# RSD_M1_HELMET_UNIT_POWER_V2.net
KiCad netlist of a schematic drawn in Altium Designer
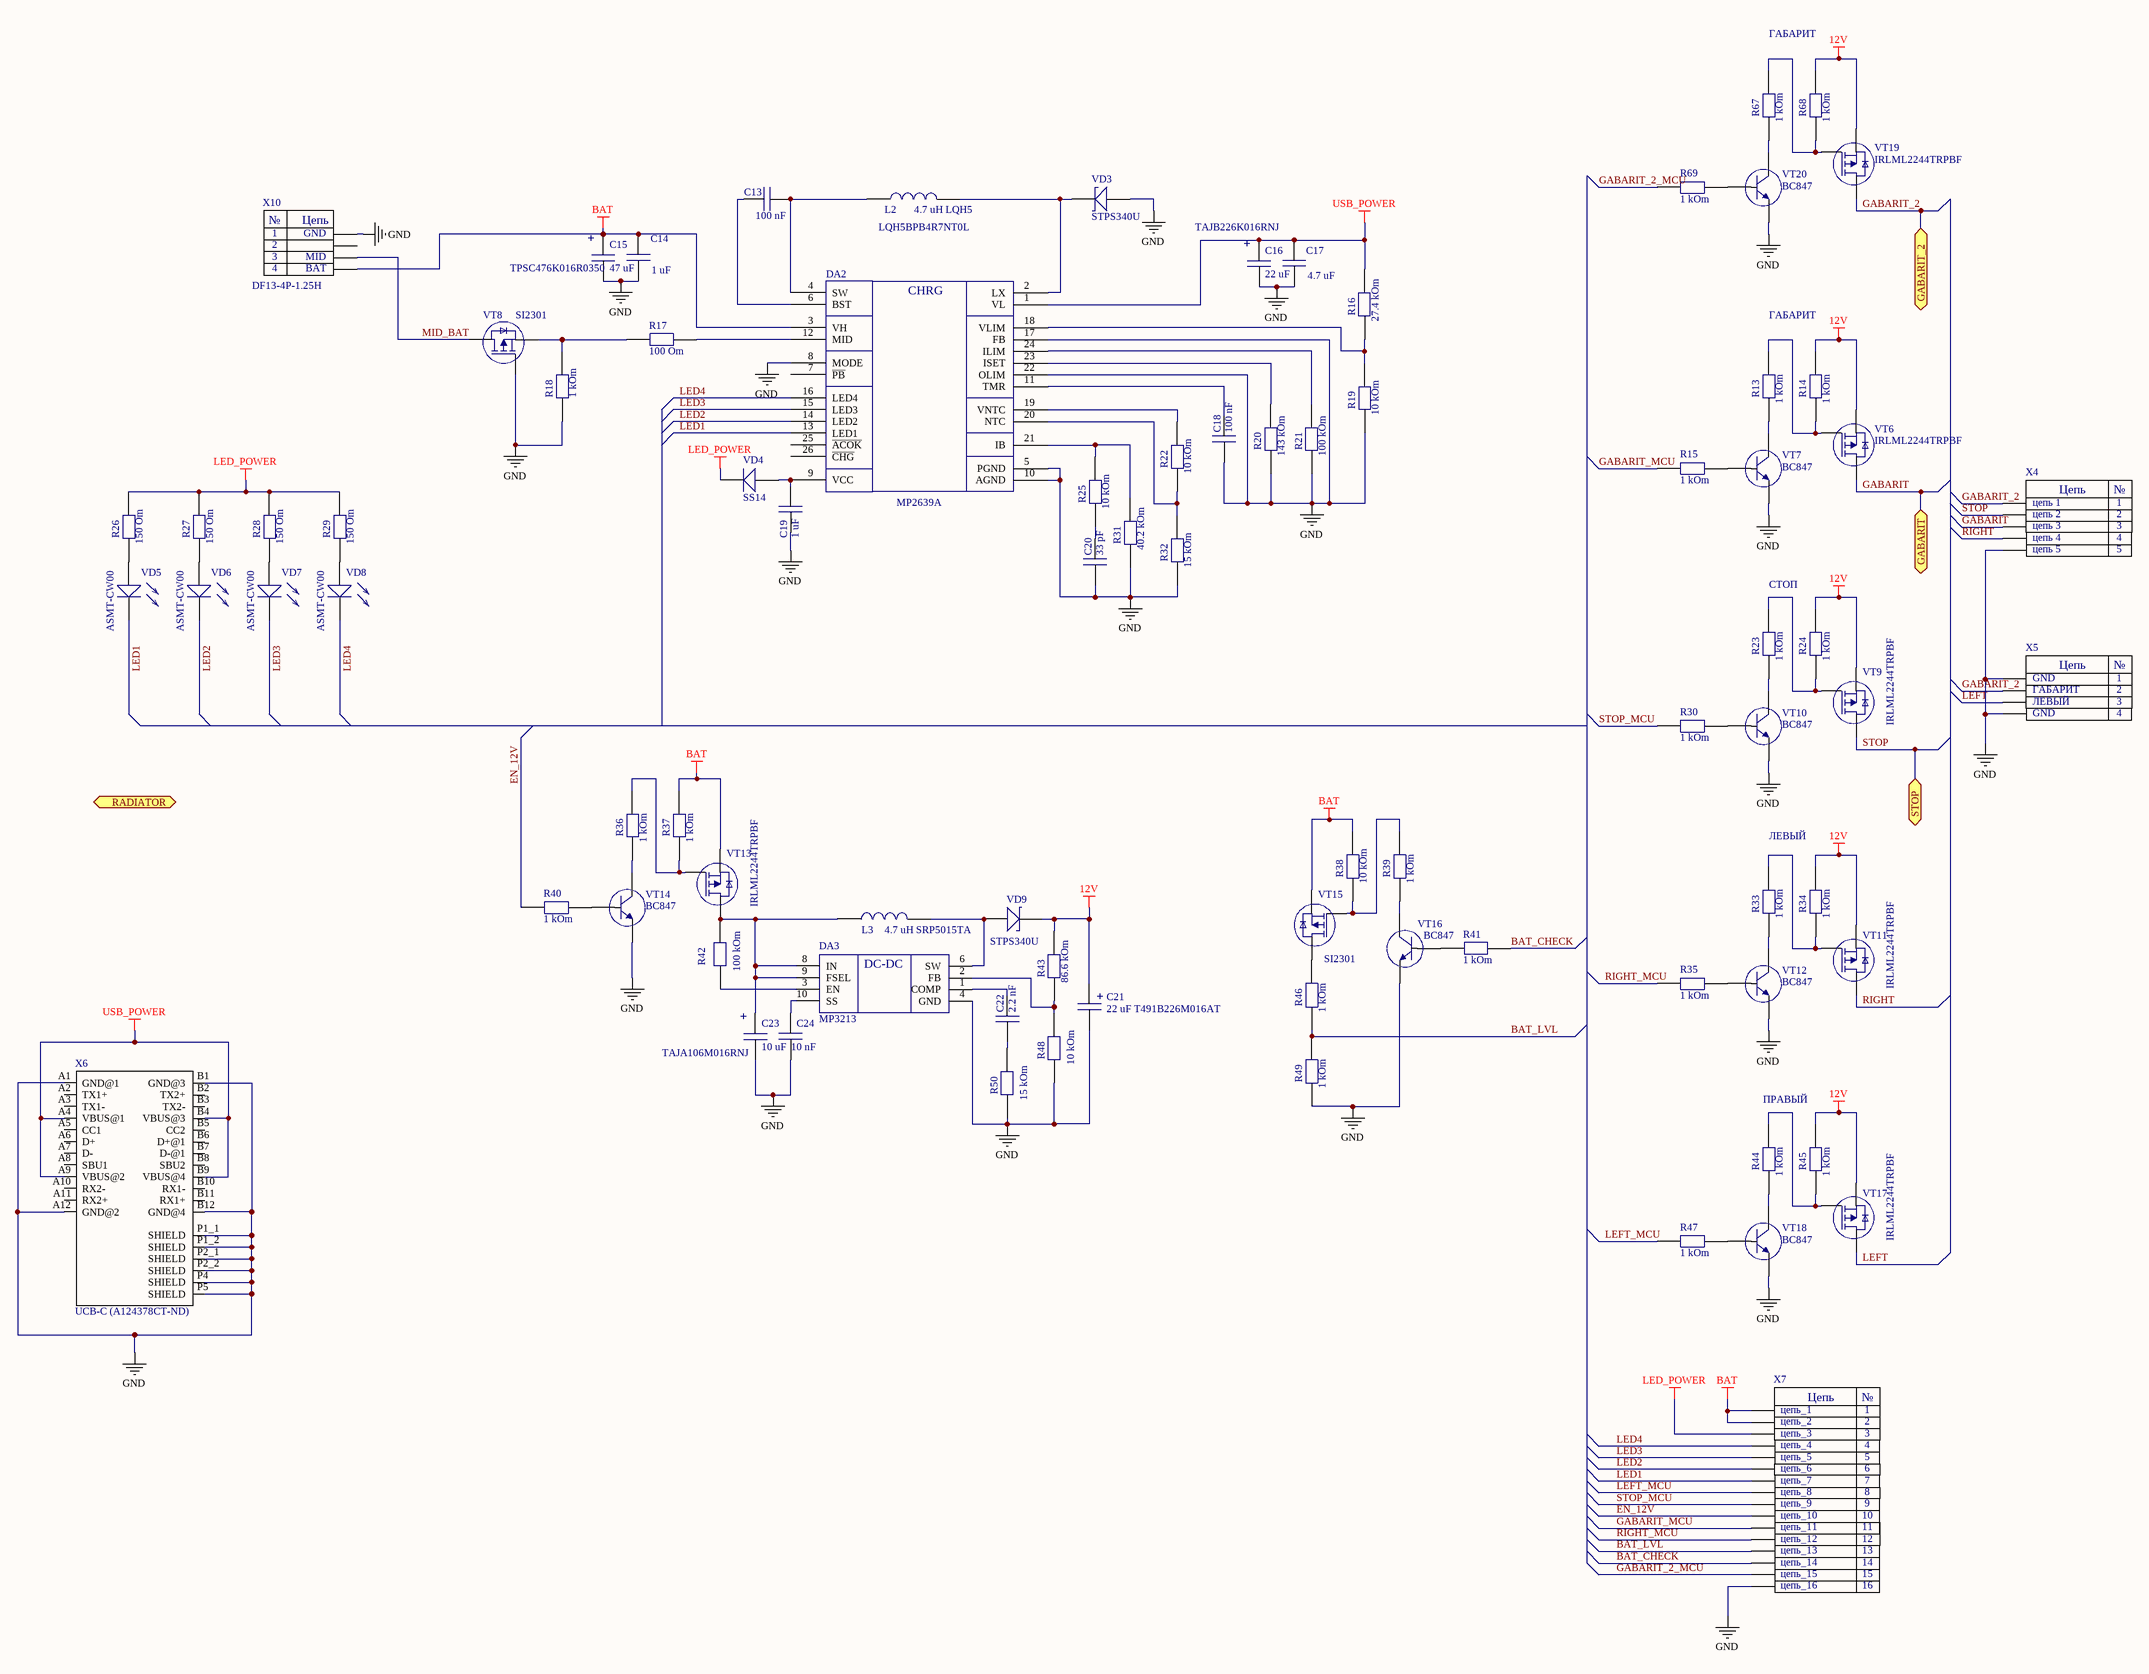
[diagram p0: RSD_M1_HELMET_UNIT_POWER_V2.SchDoc]

(export (version "E")
  (design (tool "Eeschema 10.0.6"))
  (components
    (comp (ref "C13")
      (value "100 nF")
      (footprint "CAP0603")
      (fields (field (name "Comment") "Capacitor"))
      (libsource (lib "my_library") (part "Capacitor"))
    )
    (comp (ref "C14")
      (value "1 uF")
      (footprint "CAP0603")
      (fields (field (name "Comment") "Capacitor"))
      (libsource (lib "my_library") (part "Capacitor"))
    )
    (comp (ref "C15")
      (value "47 uF")
      (footprint "tantal_case_B")
      (fields (field (name "ALTIUM_VALUE") "TPSC476K016R0350"))
      (libsource (lib "my_library") (part "Capacitor_Polar"))
    )
    (comp (ref "C16")
      (value "22 uF")
      (footprint "tantal_case_B")
      (fields (field (name "ALTIUM_VALUE") "TAJB226K016RNJ"))
      (libsource (lib "my_library") (part "Capacitor_Polar"))
    )
    (comp (ref "C17")
      (value "4.7 uF")
      (footprint "CAP0603")
      (fields (field (name "Comment") "Capacitor"))
      (libsource (lib "my_library") (part "Capacitor"))
    )
    (comp (ref "C18")
      (value "100 nF")
      (footprint "CAP0603")
      (fields (field (name "Comment") "Capacitor"))
      (libsource (lib "my_library") (part "Capacitor"))
    )
    (comp (ref "C19")
      (value "1 uF")
      (footprint "CAP0603")
      (fields (field (name "Comment") "Capacitor"))
      (libsource (lib "my_library") (part "Capacitor"))
    )
    (comp (ref "C20")
      (value "33 pF")
      (footprint "CAP0603")
      (fields (field (name "Comment") "Capacitor"))
      (libsource (lib "my_library") (part "Capacitor"))
    )
    (comp (ref "C21")
      (value "22 uF T491B226M016AT")
      (footprint "tantal_case_B")
      (fields (field (name "Comment") "Capacitor_Polar"))
      (libsource (lib "my_library") (part "Capacitor_Polar"))
    )
    (comp (ref "C22")
      (value "2.2 nF")
      (footprint "CAP0603")
      (fields (field (name "Comment") "Capacitor"))
      (libsource (lib "my_library") (part "Capacitor"))
    )
    (comp (ref "C23")
      (value "10 uF")
      (footprint "tantal_case_A")
      (fields (field (name "ALTIUM_VALUE") "TAJA106M016RNJ"))
      (libsource (lib "my_library") (part "Capacitor_Polar"))
    )
    (comp (ref "C24")
      (value "10 nF")
      (footprint "CAP0603")
      (fields (field (name "Comment") "Capacitor"))
      (libsource (lib "my_library") (part "Capacitor"))
    )
    (comp (ref "DA2")
      (value "MP2639A")
      (footprint "MP2639")
      (fields (field (name "Comment") "MP2639"))
      (libsource (lib "my_library") (part "MP2639"))
    )
    (comp (ref "DA3") (value "MP3213") (footprint "MP3213") (libsource (lib "my_library") (part "MP3213")))
    (comp (ref "L2")
      (value "4.7 uH LQH5")
      (footprint "LQH5BP")
      (fields (field (name "PN") "LQH5BPB4R7NT0L") (field (name "Comment") "coil"))
      (libsource (lib "my_library") (part "coil"))
    )
    (comp (ref "L3")
      (value "4.7 uH SRP5015TA")
      (footprint "inductor_SRP5015TA")
      (fields (field (name "Comment") "coil"))
      (libsource (lib "my_library") (part "coil"))
    )
    (comp (ref "R13")
      (value "1 kOm")
      (footprint "Res0603")
      (fields (field (name "Comment") "Resistor"))
      (libsource (lib "my_library") (part "Resistor"))
    )
    (comp (ref "R14")
      (value "1 kOm")
      (footprint "Res0603")
      (fields (field (name "Comment") "Resistor"))
      (libsource (lib "my_library") (part "Resistor"))
    )
    (comp (ref "R15")
      (value "1 kOm")
      (footprint "Res0603")
      (fields (field (name "Comment") "Resistor"))
      (libsource (lib "my_library") (part "Resistor"))
    )
    (comp (ref "R16")
      (value "27.4 kOm")
      (footprint "Res0603")
      (fields (field (name "Comment") "Resistor"))
      (libsource (lib "my_library") (part "Resistor"))
    )
    (comp (ref "R17")
      (value "100 Om")
      (footprint "Res0603")
      (fields (field (name "Comment") "Resistor"))
      (libsource (lib "my_library") (part "Resistor"))
    )
    (comp (ref "R18")
      (value "1 kOm")
      (footprint "Res0603")
      (fields (field (name "Comment") "Resistor"))
      (libsource (lib "my_library") (part "Resistor"))
    )
    (comp (ref "R19")
      (value "10 kOm")
      (footprint "Res0603")
      (fields (field (name "Comment") "Resistor"))
      (libsource (lib "my_library") (part "Resistor"))
    )
    (comp (ref "R20")
      (value "143 kOm")
      (footprint "Res0603")
      (fields (field (name "Comment") "Resistor"))
      (libsource (lib "my_library") (part "Resistor"))
    )
    (comp (ref "R21")
      (value "100 kOm")
      (footprint "Res0603")
      (fields (field (name "Comment") "Resistor"))
      (libsource (lib "my_library") (part "Resistor"))
    )
    (comp (ref "R22")
      (value "10 kOm")
      (footprint "Res0603")
      (fields (field (name "Comment") "Resistor"))
      (libsource (lib "my_library") (part "Resistor"))
    )
    (comp (ref "R23")
      (value "1 kOm")
      (footprint "Res0603")
      (fields (field (name "Comment") "Resistor"))
      (libsource (lib "my_library") (part "Resistor"))
    )
    (comp (ref "R24")
      (value "1 kOm")
      (footprint "Res0603")
      (fields (field (name "Comment") "Resistor"))
      (libsource (lib "my_library") (part "Resistor"))
    )
    (comp (ref "R25")
      (value "10 kOm")
      (footprint "Res0603")
      (fields (field (name "Comment") "Resistor"))
      (libsource (lib "my_library") (part "Resistor"))
    )
    (comp (ref "R26")
      (value "150 Om")
      (footprint "Res0603")
      (fields (field (name "Comment") "Resistor"))
      (libsource (lib "my_library") (part "Resistor"))
    )
    (comp (ref "R27")
      (value "150 Om")
      (footprint "Res0603")
      (fields (field (name "Comment") "Resistor"))
      (libsource (lib "my_library") (part "Resistor"))
    )
    (comp (ref "R28")
      (value "150 Om")
      (footprint "Res0603")
      (fields (field (name "Comment") "Resistor"))
      (libsource (lib "my_library") (part "Resistor"))
    )
    (comp (ref "R29")
      (value "150 Om")
      (footprint "Res0603")
      (fields (field (name "Comment") "Resistor"))
      (libsource (lib "my_library") (part "Resistor"))
    )
    (comp (ref "R30")
      (value "1 kOm")
      (footprint "Res0603")
      (fields (field (name "Comment") "Resistor"))
      (libsource (lib "my_library") (part "Resistor"))
    )
    (comp (ref "R31")
      (value "40.2 kOm")
      (footprint "Res0603")
      (fields (field (name "Comment") "Resistor"))
      (libsource (lib "my_library") (part "Resistor"))
    )
    (comp (ref "R32")
      (value "15 kOm")
      (footprint "Res0603")
      (fields (field (name "Comment") "Resistor"))
      (libsource (lib "my_library") (part "Resistor"))
    )
    (comp (ref "R33")
      (value "1 kOm")
      (footprint "Res0603")
      (fields (field (name "Comment") "Resistor"))
      (libsource (lib "my_library") (part "Resistor"))
    )
    (comp (ref "R34")
      (value "1 kOm")
      (footprint "Res0603")
      (fields (field (name "Comment") "Resistor"))
      (libsource (lib "my_library") (part "Resistor"))
    )
    (comp (ref "R35")
      (value "1 kOm")
      (footprint "Res0603")
      (fields (field (name "Comment") "Resistor"))
      (libsource (lib "my_library") (part "Resistor"))
    )
    (comp (ref "R36")
      (value "1 kOm")
      (footprint "Res0603")
      (fields (field (name "Comment") "Resistor"))
      (libsource (lib "my_library") (part "Resistor"))
    )
    (comp (ref "R37")
      (value "1 kOm")
      (footprint "Res0603")
      (fields (field (name "Comment") "Resistor"))
      (libsource (lib "my_library") (part "Resistor"))
    )
    (comp (ref "R38")
      (value "10 kOm")
      (footprint "Res0603")
      (fields (field (name "Comment") "Resistor"))
      (libsource (lib "my_library") (part "Resistor"))
    )
    (comp (ref "R39")
      (value "1 kOm")
      (footprint "Res0603")
      (fields (field (name "Comment") "Resistor"))
      (libsource (lib "my_library") (part "Resistor"))
    )
    (comp (ref "R40")
      (value "1 kOm")
      (footprint "Res0603")
      (fields (field (name "Comment") "Resistor"))
      (libsource (lib "my_library") (part "Resistor"))
    )
    (comp (ref "R41")
      (value "1 kOm")
      (footprint "Res0603")
      (fields (field (name "Comment") "Resistor"))
      (libsource (lib "my_library") (part "Resistor"))
    )
    (comp (ref "R42")
      (value "100 kOm")
      (footprint "Res0603")
      (fields (field (name "Comment") "Resistor"))
      (libsource (lib "my_library") (part "Resistor"))
    )
    (comp (ref "R43")
      (value "86.6 kOm")
      (footprint "Res0603")
      (fields (field (name "Comment") "Resistor"))
      (libsource (lib "my_library") (part "Resistor"))
    )
    (comp (ref "R44")
      (value "1 kOm")
      (footprint "Res0603")
      (fields (field (name "Comment") "Resistor"))
      (libsource (lib "my_library") (part "Resistor"))
    )
    (comp (ref "R45")
      (value "1 kOm")
      (footprint "Res0603")
      (fields (field (name "Comment") "Resistor"))
      (libsource (lib "my_library") (part "Resistor"))
    )
    (comp (ref "R46")
      (value "1 kOm")
      (footprint "Res0603")
      (fields (field (name "Comment") "Resistor"))
      (libsource (lib "my_library") (part "Resistor"))
    )
    (comp (ref "R47")
      (value "1 kOm")
      (footprint "Res0603")
      (fields (field (name "Comment") "Resistor"))
      (libsource (lib "my_library") (part "Resistor"))
    )
    (comp (ref "R48")
      (value "10 kOm")
      (footprint "Res0603")
      (fields (field (name "Comment") "Resistor"))
      (libsource (lib "my_library") (part "Resistor"))
    )
    (comp (ref "R49")
      (value "1 kOm")
      (footprint "Res0603")
      (fields (field (name "Comment") "Resistor"))
      (libsource (lib "my_library") (part "Resistor"))
    )
    (comp (ref "R50")
      (value "15 kOm")
      (footprint "Res0603")
      (fields (field (name "Comment") "Resistor"))
      (libsource (lib "my_library") (part "Resistor"))
    )
    (comp (ref "R67")
      (value "1 kOm")
      (footprint "Res0603")
      (fields (field (name "Comment") "Resistor"))
      (libsource (lib "my_library") (part "Resistor"))
    )
    (comp (ref "R68")
      (value "1 kOm")
      (footprint "Res0603")
      (fields (field (name "Comment") "Resistor"))
      (libsource (lib "my_library") (part "Resistor"))
    )
    (comp (ref "R69")
      (value "1 kOm")
      (footprint "Res0603")
      (fields (field (name "Comment") "Resistor"))
      (libsource (lib "my_library") (part "Resistor"))
    )
    (comp (ref "VD3")
      (value "STPS340U")
      (footprint "SMB1")
      (fields (field (name "Comment") "Schottky"))
      (libsource (lib "my_library") (part "Schottky"))
    )
    (comp (ref "VD4")
      (value "SS14")
      (footprint "SMA-F")
      (fields (field (name "Comment") "Diode"))
      (libsource (lib "my_library") (part "Diode"))
    )
    (comp (ref "VD5")
      (value "ASMT-CW00")
      (footprint "LED 0603")
      (fields (field (name "Comment") "LED"))
      (libsource (lib "my_library") (part "LED"))
    )
    (comp (ref "VD6")
      (value "ASMT-CW00")
      (footprint "LED 0603")
      (fields (field (name "Comment") "LED"))
      (libsource (lib "my_library") (part "LED"))
    )
    (comp (ref "VD7")
      (value "ASMT-CW00")
      (footprint "LED 0603")
      (fields (field (name "Comment") "LED"))
      (libsource (lib "my_library") (part "LED"))
    )
    (comp (ref "VD8")
      (value "ASMT-CW00")
      (footprint "LED 0603")
      (fields (field (name "Comment") "LED"))
      (libsource (lib "my_library") (part "LED"))
    )
    (comp (ref "VD9")
      (value "STPS340U")
      (footprint "SMB1")
      (fields (field (name "Comment") "Schottky"))
      (libsource (lib "my_library") (part "Schottky"))
    )
    (comp (ref "VT6")
      (value "IRLML2244TRPBF")
      (footprint "SOT 23")
      (fields (field (name "Comment") "MOSFET-P"))
      (libsource (lib "my_library") (part "MOSFET-P"))
    )
    (comp (ref "VT7")
      (value "BC847")
      (footprint "SOT 23")
      (fields (field (name "Comment") "NPN"))
      (libsource (lib "") (part "NPN_1"))
    )
    (comp (ref "VT8")
      (value "SI2301")
      (footprint "SOT 23")
      (fields (field (name "Comment") "MOSFET-P"))
      (libsource (lib "") (part "MOSFET-P_1"))
    )
    (comp (ref "VT9")
      (value "IRLML2244TRPBF")
      (footprint "SOT 23")
      (fields (field (name "Comment") "MOSFET-P"))
      (libsource (lib "my_library") (part "MOSFET-P"))
    )
    (comp (ref "VT10")
      (value "BC847")
      (footprint "SOT 23")
      (fields (field (name "Comment") "NPN"))
      (libsource (lib "") (part "NPN_1"))
    )
    (comp (ref "VT11")
      (value "IRLML2244TRPBF")
      (footprint "SOT 23")
      (fields (field (name "Comment") "MOSFET-P"))
      (libsource (lib "my_library") (part "MOSFET-P"))
    )
    (comp (ref "VT12")
      (value "BC847")
      (footprint "SOT 23")
      (fields (field (name "Comment") "NPN"))
      (libsource (lib "") (part "NPN_1"))
    )
    (comp (ref "VT13")
      (value "IRLML2244TRPBF")
      (footprint "SOT 23")
      (fields (field (name "Comment") "MOSFET-P"))
      (libsource (lib "my_library") (part "MOSFET-P"))
    )
    (comp (ref "VT14")
      (value "BC847")
      (footprint "SOT 23")
      (fields (field (name "Comment") "NPN"))
      (libsource (lib "") (part "NPN_1"))
    )
    (comp (ref "VT15")
      (value "SI2301")
      (footprint "SOT 23")
      (fields (field (name "Comment") "MOSFET-P"))
      (libsource (lib "my_library") (part "MOSFET-P"))
    )
    (comp (ref "VT16")
      (value "BC847")
      (footprint "SOT 23")
      (fields (field (name "Comment") "NPN"))
      (libsource (lib "my_library") (part "NPN"))
    )
    (comp (ref "VT17")
      (value "IRLML2244TRPBF")
      (footprint "SOT 23")
      (fields (field (name "Comment") "MOSFET-P"))
      (libsource (lib "my_library") (part "MOSFET-P"))
    )
    (comp (ref "VT18")
      (value "BC847")
      (footprint "SOT 23")
      (fields (field (name "Comment") "NPN"))
      (libsource (lib "") (part "NPN_1"))
    )
    (comp (ref "VT19")
      (value "IRLML2244TRPBF")
      (footprint "SOT 23")
      (fields (field (name "Comment") "MOSFET-P"))
      (libsource (lib "my_library") (part "MOSFET-P"))
    )
    (comp (ref "VT20")
      (value "BC847")
      (footprint "SOT 23")
      (fields (field (name "Comment") "NPN"))
      (libsource (lib "") (part "NPN_1"))
    )
    (comp (ref "X4")
      (value "FPC_connector_5_1")
      (footprint "FPC_5_1")
      (fields
        (field (name "1") "цепь 1")
        (field (name "2") "цепь 2")
        (field (name "3") "цепь 3")
        (field (name "4") "цепь 4")
        (field (name "5") "цепь 5")
      )
      (libsource (lib "my_library") (part "FPC_connector_5_1"))
    )
    (comp (ref "X5")
      (value "FPC_connector_4_1")
      (footprint "FPC_4_1")
      (fields
        (field (name "1") "GND")
        (field (name "2") "ГАБАРИТ")
        (field (name "3") "ЛЕВЫЙ")
        (field (name "4") "GND")
      )
      (libsource (lib "my_library") (part "FPC_connector_4_1"))
    )
    (comp (ref "X6")
      (value "UCB-C (A124378CT-ND)")
      (footprint "USB-C")
      (fields (field (name "Comment") "UCB-C"))
      (libsource (lib "my_library") (part "UCB-C"))
    )
    (comp (ref "X7")
      (value "FPC_connector_16")
      (footprint "FPC_16_0.5")
      (fields
        (field (name "16") "цепь_16")
        (field (name "1") "цепь_1")
        (field (name "2") "цепь_2")
        (field (name "3") "цепь_3")
        (field (name "4") "цепь_4")
        (field (name "5") "цепь_5")
        (field (name "6") "цепь_6")
        (field (name "7") "цепь_7")
        (field (name "8") "цепь_8")
        (field (name "9") "цепь_9")
        (field (name "10") "цепь_10")
        (field (name "11") "цепь_11")
        (field (name "12") "цепь_12")
        (field (name "13") "цепь_13")
        (field (name "14") "цепь_14")
        (field (name "15") "цепь_15")
      )
      (libsource (lib "my_library") (part "FPC_connector_16"))
    )
    (comp (ref "X10")
      (value "DF13-4P-1.25H")
      (footprint "bat_conn")
      (fields
        (field (name "1") "GND")
        (field (name "3") "MID")
        (field (name "4") "BAT")
        (field (name "Comment") "BATTERY")
      )
      (libsource (lib "my_library") (part "SWDIO"))
    )
  )
  (nets
    (net (code "1") (name "/BAT_CHECK") (class "Default")
      (node (ref "R41") (pin "2") (pinfunction "2_2") (pintype "passive"))
      (node (ref "X7") (pin "14") (pinfunction "14_14") (pintype "passive"))
    )
    (net (code "2") (name "/BAT_LVL") (class "Default")
      (node (ref "R46") (pin "1") (pinfunction "1_1") (pintype "passive"))
      (node (ref "R49") (pin "2") (pinfunction "2_2") (pintype "passive"))
      (node (ref "X7") (pin "13") (pinfunction "13_13") (pintype "passive"))
    )
    (net (code "3") (name "/EN_12V") (class "Default")
      (node (ref "R40") (pin "2") (pinfunction "2_2") (pintype "passive"))
      (node (ref "X7") (pin "10") (pinfunction "10_10") (pintype "passive"))
    )
    (net (code "4") (name "/GABARIT") (class "Default")
      (node (ref "VT6") (pin "D") (pintype "passive"))
      (node (ref "X4") (pin "3") (pinfunction "3_3") (pintype "passive"))
    )
    (net (code "5") (name "/GABARIT_2") (class "Default")
      (node (ref "VT19") (pin "D") (pintype "passive"))
      (node (ref "X4") (pin "1") (pinfunction "1_1") (pintype "passive"))
      (node (ref "X5") (pin "2") (pinfunction "2_2") (pintype "passive"))
    )
    (net (code "6") (name "/GABARIT_2_MCU") (class "Default")
      (node (ref "R69") (pin "2") (pinfunction "2_2") (pintype "passive"))
      (node (ref "X7") (pin "15") (pinfunction "15_15") (pintype "passive"))
    )
    (net (code "7") (name "/GABARIT_MCU") (class "Default")
      (node (ref "R15") (pin "2") (pinfunction "2_2") (pintype "passive"))
      (node (ref "X7") (pin "11") (pinfunction "11_11") (pintype "passive"))
    )
    (net (code "8") (name "/LED1") (class "Default")
      (node (ref "DA2") (pin "13") (pinfunction "LED1_13") (pintype "passive"))
      (node (ref "VD5") (pin "1") (pinfunction "1_1") (pintype "passive"))
      (node (ref "X7") (pin "7") (pinfunction "7_7") (pintype "passive"))
    )
    (net (code "9") (name "/LED2") (class "Default")
      (node (ref "DA2") (pin "14") (pinfunction "LED2_14") (pintype "passive"))
      (node (ref "VD6") (pin "1") (pinfunction "1_1") (pintype "passive"))
      (node (ref "X7") (pin "6") (pinfunction "6_6") (pintype "passive"))
    )
    (net (code "10") (name "/LED3") (class "Default")
      (node (ref "DA2") (pin "15") (pinfunction "LED3_15") (pintype "passive"))
      (node (ref "VD7") (pin "1") (pinfunction "1_1") (pintype "passive"))
      (node (ref "X7") (pin "5") (pinfunction "5_5") (pintype "passive"))
    )
    (net (code "11") (name "/LED4") (class "Default")
      (node (ref "DA2") (pin "16") (pinfunction "LED4_16") (pintype "passive"))
      (node (ref "VD8") (pin "1") (pinfunction "1_1") (pintype "passive"))
      (node (ref "X7") (pin "4") (pinfunction "4_4") (pintype "passive"))
    )
    (net (code "12") (name "/LEFT") (class "Default")
      (node (ref "VT17") (pin "D") (pintype "passive"))
      (node (ref "X5") (pin "3") (pinfunction "3_3") (pintype "passive"))
    )
    (net (code "13") (name "/LEFT_MCU") (class "Default")
      (node (ref "R47") (pin "2") (pinfunction "2_2") (pintype "passive"))
      (node (ref "X7") (pin "8") (pinfunction "8_8") (pintype "passive"))
    )
    (net (code "14") (name "/MID_BAT") (class "Default")
      (node (ref "VT8") (pin "D") (pintype "passive"))
      (node (ref "X10") (pin "3") (pinfunction "3_3") (pintype "passive"))
    )
    (net (code "16") (name "/RIGHT") (class "Default")
      (node (ref "VT11") (pin "D") (pintype "passive"))
      (node (ref "X4") (pin "4") (pinfunction "4_4") (pintype "passive"))
    )
    (net (code "17") (name "/RIGHT_MCU") (class "Default")
      (node (ref "R35") (pin "2") (pinfunction "2_2") (pintype "passive"))
      (node (ref "X7") (pin "12") (pinfunction "12_12") (pintype "passive"))
    )
    (net (code "18") (name "/STOP") (class "Default")
      (node (ref "VT9") (pin "D") (pintype "passive"))
      (node (ref "X4") (pin "2") (pinfunction "2_2") (pintype "passive"))
    )
    (net (code "19") (name "/STOP_MCU") (class "Default")
      (node (ref "R30") (pin "2") (pinfunction "2_2") (pintype "passive"))
      (node (ref "X7") (pin "9") (pinfunction "9_9") (pintype "passive"))
    )
    (net (code "20") (name "12V") (class "Default")
      (node (ref "C21") (pin "1") (pinfunction "1_1") (pintype "passive"))
      (node (ref "R14") (pin "2") (pinfunction "2_2") (pintype "passive"))
      (node (ref "R24") (pin "2") (pinfunction "2_2") (pintype "passive"))
      (node (ref "R34") (pin "2") (pinfunction "2_2") (pintype "passive"))
      (node (ref "R43") (pin "1") (pinfunction "1_1") (pintype "passive"))
      (node (ref "R45") (pin "2") (pinfunction "2_2") (pintype "passive"))
      (node (ref "R68") (pin "2") (pinfunction "2_2") (pintype "passive"))
      (node (ref "VD9") (pin "1") (pinfunction "1_1") (pintype "passive"))
      (node (ref "VT11") (pin "S") (pintype "passive"))
      (node (ref "VT17") (pin "S") (pintype "passive"))
      (node (ref "VT19") (pin "S") (pintype "passive"))
      (node (ref "VT6") (pin "S") (pintype "passive"))
      (node (ref "VT9") (pin "S") (pintype "passive"))
    )
    (net (code "21") (name "BAT") (class "Default")
      (node (ref "C14") (pin "2") (pinfunction "2_2") (pintype "passive"))
      (node (ref "C15") (pin "1") (pinfunction "1_1") (pintype "passive"))
      (node (ref "DA2") (pin "3") (pinfunction "VH_3") (pintype "passive"))
      (node (ref "R37") (pin "2") (pinfunction "2_2") (pintype "passive"))
      (node (ref "R38") (pin "2") (pinfunction "2_2") (pintype "passive"))
      (node (ref "VT13") (pin "S") (pintype "passive"))
      (node (ref "VT15") (pin "S") (pintype "passive"))
      (node (ref "X10") (pin "4") (pinfunction "4_4") (pintype "passive"))
      (node (ref "X7") (pin "1") (pinfunction "1_1") (pintype "passive"))
      (node (ref "X7") (pin "2") (pinfunction "2_2") (pintype "passive"))
    )
    (net (code "22") (name "GND") (class "Default")
      (node (ref "C14") (pin "1") (pinfunction "1_1") (pintype "passive"))
      (node (ref "C15") (pin "2") (pinfunction "2_2") (pintype "passive"))
      (node (ref "C16") (pin "2") (pinfunction "2_2") (pintype "passive"))
      (node (ref "C17") (pin "1") (pinfunction "1_1") (pintype "passive"))
      (node (ref "C18") (pin "1") (pinfunction "1_1") (pintype "passive"))
      (node (ref "C19") (pin "1") (pinfunction "1_1") (pintype "passive"))
      (node (ref "C20") (pin "1") (pinfunction "1_1") (pintype "passive"))
      (node (ref "C21") (pin "2") (pinfunction "2_2") (pintype "passive"))
      (node (ref "C23") (pin "2") (pinfunction "2_2") (pintype "passive"))
      (node (ref "C24") (pin "1") (pinfunction "1_1") (pintype "passive"))
      (node (ref "DA2") (pin "10") (pinfunction "AGND_10") (pintype "passive"))
      (node (ref "DA2") (pin "17") (pinfunction "FB_17") (pintype "passive"))
      (node (ref "DA2") (pin "22") (pinfunction "OLIM_22") (pintype "passive"))
      (node (ref "DA2") (pin "5") (pinfunction "PGND_5") (pintype "passive"))
      (node (ref "DA2") (pin "8") (pinfunction "MODE_8") (pintype "passive"))
      (node (ref "DA3") (pin "4") (pinfunction "GND_4") (pintype "passive"))
      (node (ref "R18") (pin "1") (pinfunction "1_1") (pintype "passive"))
      (node (ref "R19") (pin "1") (pinfunction "1_1") (pintype "passive"))
      (node (ref "R20") (pin "1") (pinfunction "1_1") (pintype "passive"))
      (node (ref "R21") (pin "2") (pinfunction "2_2") (pintype "passive"))
      (node (ref "R31") (pin "1") (pinfunction "1_1") (pintype "passive"))
      (node (ref "R32") (pin "1") (pinfunction "1_1") (pintype "passive"))
      (node (ref "R48") (pin "2") (pinfunction "2_2") (pintype "passive"))
      (node (ref "R49") (pin "1") (pinfunction "1_1") (pintype "passive"))
      (node (ref "R50") (pin "2") (pinfunction "2_2") (pintype "passive"))
      (node (ref "VD3") (pin "2") (pinfunction "2_2") (pintype "passive"))
      (node (ref "VT10") (pin "E") (pinfunction "E_E") (pintype "passive"))
      (node (ref "VT12") (pin "E") (pinfunction "E_E") (pintype "passive"))
      (node (ref "VT14") (pin "E") (pinfunction "E_E") (pintype "passive"))
      (node (ref "VT16") (pin "E") (pinfunction "E_E") (pintype "passive"))
      (node (ref "VT18") (pin "E") (pinfunction "E_E") (pintype "passive"))
      (node (ref "VT20") (pin "E") (pinfunction "E_E") (pintype "passive"))
      (node (ref "VT7") (pin "E") (pinfunction "E_E") (pintype "passive"))
      (node (ref "VT8") (pin "G") (pintype "passive"))
      (node (ref "X10") (pin "1") (pinfunction "1_1") (pintype "passive"))
      (node (ref "X4") (pin "5") (pinfunction "5_5") (pintype "passive"))
      (node (ref "X5") (pin "1") (pinfunction "1_1") (pintype "passive"))
      (node (ref "X5") (pin "4") (pinfunction "4_4") (pintype "passive"))
      (node (ref "X6") (pin "A1") (pinfunction "GND@1_A1") (pintype "passive"))
      (node (ref "X6") (pin "A12") (pinfunction "GND@2_A12") (pintype "passive"))
      (node (ref "X6") (pin "B1") (pinfunction "GND@3_B1") (pintype "passive"))
      (node (ref "X6") (pin "B12") (pinfunction "GND@4_B12") (pintype "passive"))
      (node (ref "X6") (pin "P1_1") (pinfunction "SHIELD_P1_1") (pintype "passive"))
      (node (ref "X6") (pin "P1_2") (pinfunction "SHIELD_P1_2") (pintype "passive"))
      (node (ref "X6") (pin "P2_1") (pinfunction "SHIELD_P2_1") (pintype "passive"))
      (node (ref "X6") (pin "P2_2") (pinfunction "SHIELD_P2_2") (pintype "passive"))
      (node (ref "X6") (pin "P4") (pinfunction "SHIELD_P4") (pintype "passive"))
      (node (ref "X6") (pin "P5") (pinfunction "SHIELD_P5") (pintype "passive"))
      (node (ref "X7") (pin "16") (pinfunction "16_16") (pintype "passive"))
    )
    (net (code "23") (name "LED_POWER") (class "Default")
      (node (ref "R26") (pin "2") (pinfunction "2_2") (pintype "passive"))
      (node (ref "R27") (pin "2") (pinfunction "2_2") (pintype "passive"))
      (node (ref "R28") (pin "2") (pinfunction "2_2") (pintype "passive"))
      (node (ref "R29") (pin "2") (pinfunction "2_2") (pintype "passive"))
      (node (ref "VD4") (pin "1") (pinfunction "1_1") (pintype "passive"))
      (node (ref "X7") (pin "3") (pinfunction "3_3") (pintype "passive"))
    )
    (net (code "24") (name "Net-(C20-Pad2)") (class "Default")
      (node (ref "C20") (pin "2") (pinfunction "2_2") (pintype "passive"))
      (node (ref "R25") (pin "1") (pinfunction "1_1") (pintype "passive"))
    )
    (net (code "25") (name "Net-(C22-Pad2)") (class "Default")
      (node (ref "C22") (pin "2") (pinfunction "2_2") (pintype "passive"))
      (node (ref "R50") (pin "1") (pinfunction "1_1") (pintype "passive"))
    )
    (net (code "26") (name "Net-(DA2-BST)") (class "Default")
      (node (ref "C13") (pin "1") (pinfunction "1_1") (pintype "passive"))
      (node (ref "DA2") (pin "6") (pinfunction "BST_6") (pintype "passive"))
    )
    (net (code "27") (name "Net-(DA2-IB)") (class "Default")
      (node (ref "DA2") (pin "21") (pinfunction "IB_21") (pintype "passive"))
      (node (ref "R25") (pin "2") (pinfunction "2_2") (pintype "passive"))
      (node (ref "R31") (pin "2") (pinfunction "2_2") (pintype "passive"))
    )
    (net (code "28") (name "Net-(DA2-ILIM)") (class "Default")
      (node (ref "DA2") (pin "24") (pinfunction "ILIM_24") (pintype "passive"))
      (node (ref "R21") (pin "1") (pinfunction "1_1") (pintype "passive"))
    )
    (net (code "29") (name "Net-(DA2-ISET)") (class "Default")
      (node (ref "DA2") (pin "23") (pinfunction "ISET_23") (pintype "passive"))
      (node (ref "R20") (pin "2") (pinfunction "2_2") (pintype "passive"))
    )
    (net (code "30") (name "Net-(DA2-LX)") (class "Default")
      (node (ref "DA2") (pin "2") (pinfunction "LX_2") (pintype "passive"))
      (node (ref "L2") (pin "2") (pinfunction "2_2") (pintype "passive"))
      (node (ref "VD3") (pin "1") (pinfunction "1_1") (pintype "passive"))
    )
    (net (code "31") (name "Net-(DA2-MID)") (class "Default")
      (node (ref "DA2") (pin "12") (pinfunction "MID_12") (pintype "passive"))
      (node (ref "R17") (pin "2") (pinfunction "2_2") (pintype "passive"))
    )
    (net (code "32") (name "Net-(DA2-NTC)") (class "Default")
      (node (ref "DA2") (pin "20") (pinfunction "NTC_20") (pintype "passive"))
      (node (ref "R22") (pin "1") (pinfunction "1_1") (pintype "passive"))
      (node (ref "R32") (pin "2") (pinfunction "2_2") (pintype "passive"))
    )
    (net (code "33") (name "Net-(DA2-SW)") (class "Default")
      (node (ref "C13") (pin "2") (pinfunction "2_2") (pintype "passive"))
      (node (ref "DA2") (pin "4") (pinfunction "SW_4") (pintype "passive"))
      (node (ref "L2") (pin "1") (pinfunction "1_1") (pintype "passive"))
    )
    (net (code "34") (name "Net-(DA2-TMR)") (class "Default")
      (node (ref "C18") (pin "2") (pinfunction "2_2") (pintype "passive"))
      (node (ref "DA2") (pin "11") (pinfunction "TMR_11") (pintype "passive"))
    )
    (net (code "35") (name "Net-(DA2-VCC)") (class "Default")
      (node (ref "C19") (pin "2") (pinfunction "2_2") (pintype "passive"))
      (node (ref "DA2") (pin "9") (pinfunction "VCC_9") (pintype "passive"))
      (node (ref "VD4") (pin "2") (pinfunction "2_2") (pintype "passive"))
    )
    (net (code "36") (name "Net-(DA2-VLIM)") (class "Default")
      (node (ref "DA2") (pin "18") (pinfunction "VLIM_18") (pintype "passive"))
      (node (ref "R16") (pin "2") (pinfunction "2_2") (pintype "passive"))
      (node (ref "R19") (pin "2") (pinfunction "2_2") (pintype "passive"))
    )
    (net (code "37") (name "Net-(DA2-VNTC)") (class "Default")
      (node (ref "DA2") (pin "19") (pinfunction "VNTC_19") (pintype "passive"))
      (node (ref "R22") (pin "2") (pinfunction "2_2") (pintype "passive"))
    )
    (net (code "38") (name "Net-(DA3-COMP)") (class "Default")
      (node (ref "C22") (pin "1") (pinfunction "1_1") (pintype "passive"))
      (node (ref "DA3") (pin "1") (pinfunction "COMP_1") (pintype "passive"))
    )
    (net (code "39") (name "Net-(DA3-EN)") (class "Default")
      (node (ref "DA3") (pin "3") (pinfunction "EN_3") (pintype "passive"))
      (node (ref "R42") (pin "2") (pinfunction "2_2") (pintype "passive"))
    )
    (net (code "40") (name "Net-(DA3-FB)") (class "Default")
      (node (ref "DA3") (pin "2") (pinfunction "FB_2") (pintype "passive"))
      (node (ref "R43") (pin "2") (pinfunction "2_2") (pintype "passive"))
      (node (ref "R48") (pin "1") (pinfunction "1_1") (pintype "passive"))
    )
    (net (code "41") (name "Net-(DA3-FSEL)") (class "Default")
      (node (ref "C23") (pin "1") (pinfunction "1_1") (pintype "passive"))
      (node (ref "DA3") (pin "8") (pinfunction "IN_8") (pintype "passive"))
      (node (ref "DA3") (pin "9") (pinfunction "FSEL_9") (pintype "passive"))
      (node (ref "L3") (pin "1") (pinfunction "1_1") (pintype "passive"))
      (node (ref "R42") (pin "1") (pinfunction "1_1") (pintype "passive"))
      (node (ref "VT13") (pin "D") (pintype "passive"))
    )
    (net (code "42") (name "Net-(DA3-SS)") (class "Default")
      (node (ref "C24") (pin "2") (pinfunction "2_2") (pintype "passive"))
      (node (ref "DA3") (pin "10") (pinfunction "SS_10") (pintype "passive"))
    )
    (net (code "43") (name "Net-(DA3-SW)") (class "Default")
      (node (ref "DA3") (pin "6") (pinfunction "SW_6") (pintype "passive"))
      (node (ref "L3") (pin "2") (pinfunction "2_2") (pintype "passive"))
      (node (ref "VD9") (pin "2") (pinfunction "2_2") (pintype "passive"))
    )
    (net (code "44") (name "Net-(R13-Pad1)") (class "Default")
      (node (ref "R13") (pin "1") (pinfunction "1_1") (pintype "passive"))
      (node (ref "VT7") (pin "K") (pinfunction "K_K") (pintype "passive"))
    )
    (net (code "45") (name "Net-(R13-Pad2)") (class "Default")
      (node (ref "R13") (pin "2") (pinfunction "2_2") (pintype "passive"))
      (node (ref "R14") (pin "1") (pinfunction "1_1") (pintype "passive"))
      (node (ref "VT6") (pin "G") (pintype "passive"))
    )
    (net (code "46") (name "Net-(R15-Pad1)") (class "Default")
      (node (ref "R15") (pin "1") (pinfunction "1_1") (pintype "passive"))
      (node (ref "VT7") (pin "B") (pinfunction "B_B") (pintype "passive"))
    )
    (net (code "47") (name "Net-(R17-Pad1)") (class "Default")
      (node (ref "R17") (pin "1") (pinfunction "1_1") (pintype "passive"))
      (node (ref "R18") (pin "2") (pinfunction "2_2") (pintype "passive"))
      (node (ref "VT8") (pin "S") (pintype "passive"))
    )
    (net (code "48") (name "Net-(R23-Pad1)") (class "Default")
      (node (ref "R23") (pin "1") (pinfunction "1_1") (pintype "passive"))
      (node (ref "VT10") (pin "K") (pinfunction "K_K") (pintype "passive"))
    )
    (net (code "49") (name "Net-(R23-Pad2)") (class "Default")
      (node (ref "R23") (pin "2") (pinfunction "2_2") (pintype "passive"))
      (node (ref "R24") (pin "1") (pinfunction "1_1") (pintype "passive"))
      (node (ref "VT9") (pin "G") (pintype "passive"))
    )
    (net (code "50") (name "Net-(R26-Pad1)") (class "Default")
      (node (ref "R26") (pin "1") (pinfunction "1_1") (pintype "passive"))
      (node (ref "VD5") (pin "2") (pinfunction "2_2") (pintype "passive"))
    )
    (net (code "51") (name "Net-(R27-Pad1)") (class "Default")
      (node (ref "R27") (pin "1") (pinfunction "1_1") (pintype "passive"))
      (node (ref "VD6") (pin "2") (pinfunction "2_2") (pintype "passive"))
    )
    (net (code "52") (name "Net-(R28-Pad1)") (class "Default")
      (node (ref "R28") (pin "1") (pinfunction "1_1") (pintype "passive"))
      (node (ref "VD7") (pin "2") (pinfunction "2_2") (pintype "passive"))
    )
    (net (code "53") (name "Net-(R29-Pad1)") (class "Default")
      (node (ref "R29") (pin "1") (pinfunction "1_1") (pintype "passive"))
      (node (ref "VD8") (pin "2") (pinfunction "2_2") (pintype "passive"))
    )
    (net (code "54") (name "Net-(R30-Pad1)") (class "Default")
      (node (ref "R30") (pin "1") (pinfunction "1_1") (pintype "passive"))
      (node (ref "VT10") (pin "B") (pinfunction "B_B") (pintype "passive"))
    )
    (net (code "55") (name "Net-(R33-Pad1)") (class "Default")
      (node (ref "R33") (pin "1") (pinfunction "1_1") (pintype "passive"))
      (node (ref "VT12") (pin "K") (pinfunction "K_K") (pintype "passive"))
    )
    (net (code "56") (name "Net-(R33-Pad2)") (class "Default")
      (node (ref "R33") (pin "2") (pinfunction "2_2") (pintype "passive"))
      (node (ref "R34") (pin "1") (pinfunction "1_1") (pintype "passive"))
      (node (ref "VT11") (pin "G") (pintype "passive"))
    )
    (net (code "57") (name "Net-(R35-Pad1)") (class "Default")
      (node (ref "R35") (pin "1") (pinfunction "1_1") (pintype "passive"))
      (node (ref "VT12") (pin "B") (pinfunction "B_B") (pintype "passive"))
    )
    (net (code "58") (name "Net-(R36-Pad1)") (class "Default")
      (node (ref "R36") (pin "1") (pinfunction "1_1") (pintype "passive"))
      (node (ref "VT14") (pin "K") (pinfunction "K_K") (pintype "passive"))
    )
    (net (code "59") (name "Net-(R36-Pad2)") (class "Default")
      (node (ref "R36") (pin "2") (pinfunction "2_2") (pintype "passive"))
      (node (ref "R37") (pin "1") (pinfunction "1_1") (pintype "passive"))
      (node (ref "VT13") (pin "G") (pintype "passive"))
    )
    (net (code "60") (name "Net-(R38-Pad1)") (class "Default")
      (node (ref "R38") (pin "1") (pinfunction "1_1") (pintype "passive"))
      (node (ref "R39") (pin "2") (pinfunction "2_2") (pintype "passive"))
      (node (ref "VT15") (pin "G") (pintype "passive"))
    )
    (net (code "61") (name "Net-(R39-Pad1)") (class "Default")
      (node (ref "R39") (pin "1") (pinfunction "1_1") (pintype "passive"))
      (node (ref "VT16") (pin "K") (pinfunction "K_K") (pintype "passive"))
    )
    (net (code "62") (name "Net-(R40-Pad1)") (class "Default")
      (node (ref "R40") (pin "1") (pinfunction "1_1") (pintype "passive"))
      (node (ref "VT14") (pin "B") (pinfunction "B_B") (pintype "passive"))
    )
    (net (code "63") (name "Net-(R41-Pad1)") (class "Default")
      (node (ref "R41") (pin "1") (pinfunction "1_1") (pintype "passive"))
      (node (ref "VT16") (pin "B") (pinfunction "B_B") (pintype "passive"))
    )
    (net (code "64") (name "Net-(R44-Pad1)") (class "Default")
      (node (ref "R44") (pin "1") (pinfunction "1_1") (pintype "passive"))
      (node (ref "VT18") (pin "K") (pinfunction "K_K") (pintype "passive"))
    )
    (net (code "65") (name "Net-(R44-Pad2)") (class "Default")
      (node (ref "R44") (pin "2") (pinfunction "2_2") (pintype "passive"))
      (node (ref "R45") (pin "1") (pinfunction "1_1") (pintype "passive"))
      (node (ref "VT17") (pin "G") (pintype "passive"))
    )
    (net (code "66") (name "Net-(R46-Pad2)") (class "Default")
      (node (ref "R46") (pin "2") (pinfunction "2_2") (pintype "passive"))
      (node (ref "VT15") (pin "D") (pintype "passive"))
    )
    (net (code "67") (name "Net-(R47-Pad1)") (class "Default")
      (node (ref "R47") (pin "1") (pinfunction "1_1") (pintype "passive"))
      (node (ref "VT18") (pin "B") (pinfunction "B_B") (pintype "passive"))
    )
    (net (code "68") (name "Net-(R67-Pad1)") (class "Default")
      (node (ref "R67") (pin "1") (pinfunction "1_1") (pintype "passive"))
      (node (ref "VT20") (pin "K") (pinfunction "K_K") (pintype "passive"))
    )
    (net (code "69") (name "Net-(R67-Pad2)") (class "Default")
      (node (ref "R67") (pin "2") (pinfunction "2_2") (pintype "passive"))
      (node (ref "R68") (pin "1") (pinfunction "1_1") (pintype "passive"))
      (node (ref "VT19") (pin "G") (pintype "passive"))
    )
    (net (code "70") (name "Net-(R69-Pad1)") (class "Default")
      (node (ref "R69") (pin "1") (pinfunction "1_1") (pintype "passive"))
      (node (ref "VT20") (pin "B") (pinfunction "B_B") (pintype "passive"))
    )
    (net (code "71") (name "USB_POWER") (class "Default")
      (node (ref "C16") (pin "1") (pinfunction "1_1") (pintype "passive"))
      (node (ref "C17") (pin "2") (pinfunction "2_2") (pintype "passive"))
      (node (ref "DA2") (pin "1") (pinfunction "VL_1") (pintype "passive"))
      (node (ref "R16") (pin "1") (pinfunction "1_1") (pintype "passive"))
      (node (ref "X6") (pin "A4") (pinfunction "VBUS@1_A4") (pintype "passive"))
      (node (ref "X6") (pin "A9") (pinfunction "VBUS@2_A9") (pintype "passive"))
      (node (ref "X6") (pin "B4") (pinfunction "VBUS@3_B4") (pintype "passive"))
      (node (ref "X6") (pin "B9") (pinfunction "VBUS@4_B9") (pintype "passive"))
    )
    (net (code "72") (name "unconnected-(DA2-~{ACOK}-Pad25)") (class "Default")
      (node (ref "DA2") (pin "25") (pinfunction "~{ACOK}_25") (pintype "passive"))
    )
    (net (code "73") (name "unconnected-(DA2-~{CHG}-Pad26)") (class "Default")
      (node (ref "DA2") (pin "26") (pinfunction "~{CHG}_26") (pintype "passive"))
    )
    (net (code "74") (name "unconnected-(DA2-~{PB}-Pad7)") (class "Default")
      (node (ref "DA2") (pin "7") (pinfunction "~{PB}_7") (pintype "passive"))
    )
    (net (code "75") (name "unconnected-(X6-CC1-PadA5)") (class "Default")
      (node (ref "X6") (pin "A5") (pinfunction "CC1_A5") (pintype "passive"))
    )
    (net (code "76") (name "unconnected-(X6-CC2-PadB5)") (class "Default")
      (node (ref "X6") (pin "B5") (pinfunction "CC2_B5") (pintype "passive"))
    )
    (net (code "77") (name "unconnected-(X6-D+-PadA6)") (class "Default")
      (node (ref "X6") (pin "A6") (pinfunction "D+_A6") (pintype "passive"))
    )
    (net (code "78") (name "unconnected-(X6-D+@1-PadB6)") (class "Default")
      (node (ref "X6") (pin "B6") (pinfunction "D+@1_B6") (pintype "passive"))
    )
    (net (code "79") (name "unconnected-(X6-D--PadA7)") (class "Default")
      (node (ref "X6") (pin "A7") (pinfunction "D-_A7") (pintype "passive"))
    )
    (net (code "80") (name "unconnected-(X6-D-@1-PadB7)") (class "Default")
      (node (ref "X6") (pin "B7") (pinfunction "D-@1_B7") (pintype "passive"))
    )
    (net (code "81") (name "unconnected-(X6-RX1+-PadB11)") (class "Default")
      (node (ref "X6") (pin "B11") (pinfunction "RX1+_B11") (pintype "passive"))
    )
    (net (code "82") (name "unconnected-(X6-RX1--PadB10)") (class "Default")
      (node (ref "X6") (pin "B10") (pinfunction "RX1-_B10") (pintype "passive"))
    )
    (net (code "83") (name "unconnected-(X6-RX2+-PadA11)") (class "Default")
      (node (ref "X6") (pin "A11") (pinfunction "RX2+_A11") (pintype "passive"))
    )
    (net (code "84") (name "unconnected-(X6-RX2--PadA10)") (class "Default")
      (node (ref "X6") (pin "A10") (pinfunction "RX2-_A10") (pintype "passive"))
    )
    (net (code "85") (name "unconnected-(X6-SBU1-PadA8)") (class "Default")
      (node (ref "X6") (pin "A8") (pinfunction "SBU1_A8") (pintype "passive"))
    )
    (net (code "86") (name "unconnected-(X6-SBU2-PadB8)") (class "Default")
      (node (ref "X6") (pin "B8") (pinfunction "SBU2_B8") (pintype "passive"))
    )
    (net (code "87") (name "unconnected-(X6-TX1+-PadA2)") (class "Default")
      (node (ref "X6") (pin "A2") (pinfunction "TX1+_A2") (pintype "passive"))
    )
    (net (code "88") (name "unconnected-(X6-TX1--PadA3)") (class "Default")
      (node (ref "X6") (pin "A3") (pinfunction "TX1-_A3") (pintype "passive"))
    )
    (net (code "89") (name "unconnected-(X6-TX2+-PadB2)") (class "Default")
      (node (ref "X6") (pin "B2") (pinfunction "TX2+_B2") (pintype "passive"))
    )
    (net (code "90") (name "unconnected-(X6-TX2--PadB3)") (class "Default")
      (node (ref "X6") (pin "B3") (pinfunction "TX2-_B3") (pintype "passive"))
    )
    (net (code "91") (name "unconnected-(X10-Pad2)") (class "Default")
      (node (ref "X10") (pin "2") (pinfunction "2_2") (pintype "passive"))
    )
  )
)
